# AUDIO.net
KiCad netlist of a schematic drawn in Altium Designer
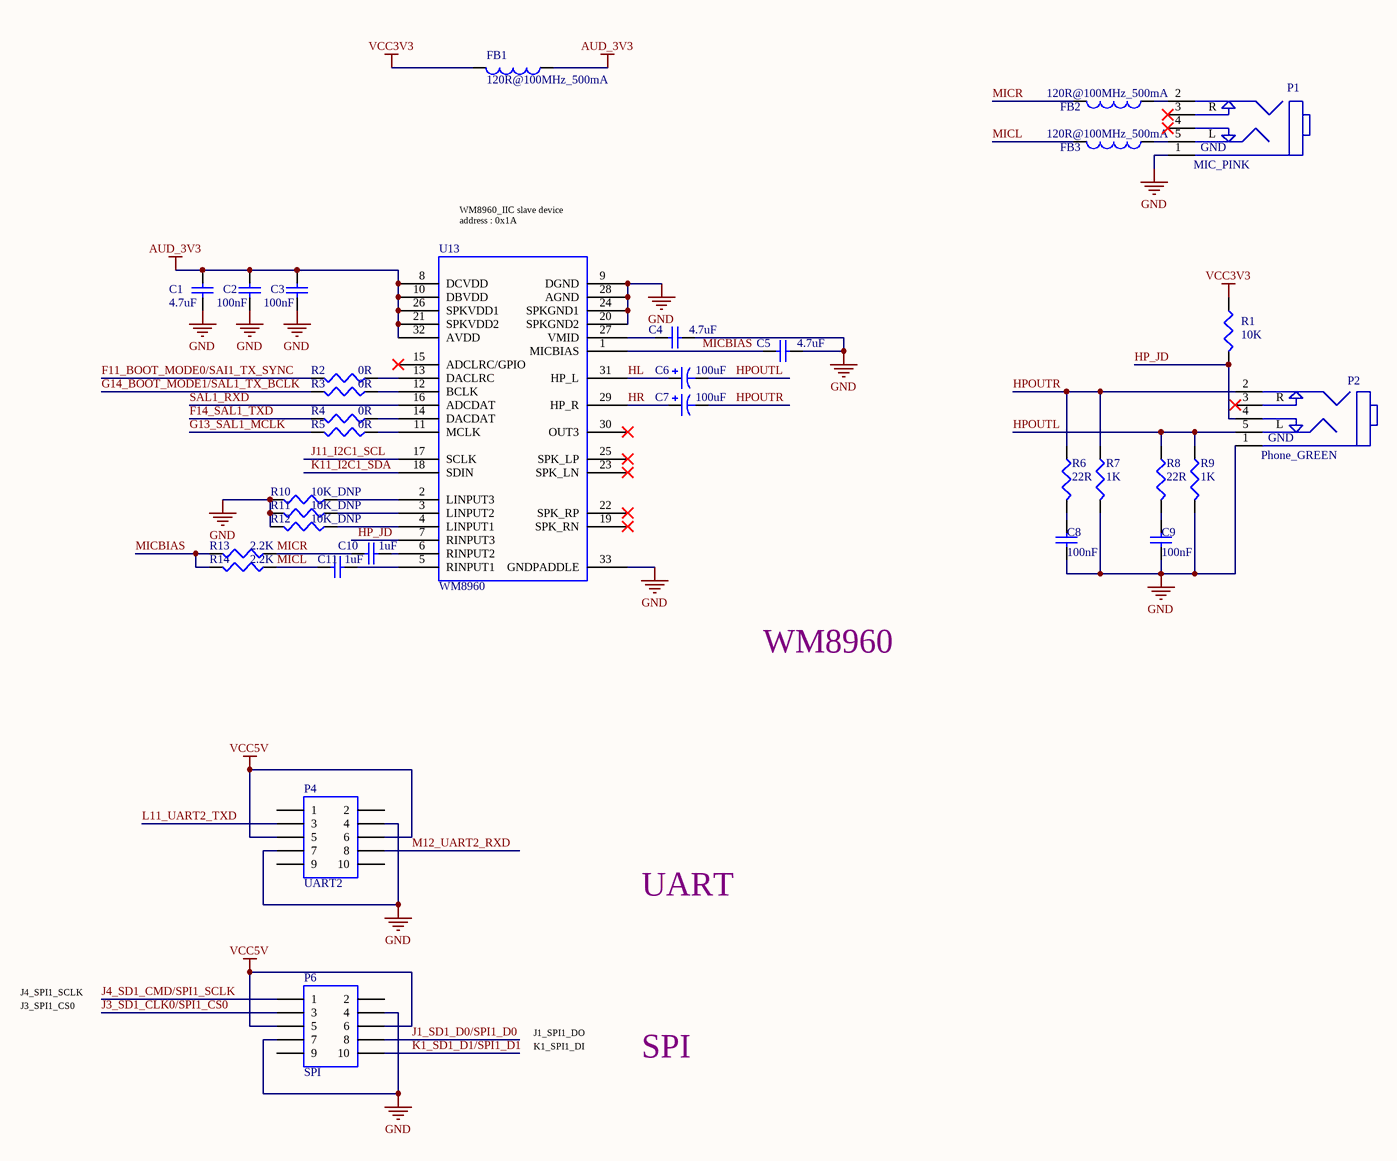
[diagram p0: AUDIO.SchDoc]

(export (version "E")
  (design (tool "Eeschema 10.0.6"))
  (components
    (comp (ref "C1")
      (value "4.7uF")
      (footprint "0603C+")
      (description "Capacitor")
      (fields (field (name "PUBLISHER") "Altium Limited"))
      (libsource (lib "Miscellaneous Devices") (part "Cap"))
    )
    (comp (ref "C2")
      (value "100nF")
      (footprint "0603C+")
      (description "Capacitor")
      (fields (field (name "PUBLISHER") "Altium Limited"))
      (libsource (lib "Miscellaneous Devices") (part "Cap"))
    )
    (comp (ref "C3")
      (value "100nF")
      (footprint "0603C+")
      (description "Capacitor")
      (fields (field (name "PUBLISHER") "Altium Limited"))
      (libsource (lib "Miscellaneous Devices") (part "Cap"))
    )
    (comp (ref "C4")
      (value "4.7uF")
      (footprint "0603C+")
      (description "Capacitor")
      (fields (field (name "PUBLISHER") "Altium Limited"))
      (libsource (lib "Miscellaneous Devices") (part "Cap"))
    )
    (comp (ref "C5")
      (value "4.7uF")
      (footprint "0603C+")
      (description "Capacitor")
      (fields (field (name "PUBLISHER") "Altium Limited"))
      (libsource (lib "Miscellaneous Devices") (part "Cap"))
    )
    (comp (ref "C6")
      (value "100uF")
      (footprint "TC3528B")
      (description "Polarized Capacitor (Radial)")
      (fields (field (name "PUBLISHER") "Altium Limited"))
      (libsource (lib "Miscellaneous Devices") (part "Cap Pol1"))
    )
    (comp (ref "C7")
      (value "100uF")
      (footprint "TC3528B")
      (description "Polarized Capacitor (Radial)")
      (fields (field (name "PUBLISHER") "Altium Limited"))
      (libsource (lib "Miscellaneous Devices") (part "Cap Pol1"))
    )
    (comp (ref "C8")
      (value "100nF")
      (footprint "0603C+")
      (description "Capacitor")
      (fields (field (name "PUBLISHER") "Altium Limited"))
      (libsource (lib "Miscellaneous Devices") (part "Cap"))
    )
    (comp (ref "C9")
      (value "100nF")
      (footprint "0603C+")
      (description "Capacitor")
      (fields (field (name "PUBLISHER") "Altium Limited"))
      (libsource (lib "Miscellaneous Devices") (part "Cap"))
    )
    (comp (ref "C10")
      (value "1uF")
      (footprint "0603C+")
      (description "Capacitor")
      (fields (field (name "PUBLISHER") "Altium Limited"))
      (libsource (lib "Miscellaneous Devices") (part "Cap"))
    )
    (comp (ref "C11")
      (value "1uF")
      (footprint "0603C+")
      (description "Capacitor")
      (fields (field (name "PUBLISHER") "Altium Limited"))
      (libsource (lib "Miscellaneous Devices") (part "Cap"))
    )
    (comp (ref "FB1")
      (value "120R@100MHz_500mA")
      (footprint "0603R+")
      (description "Inductor")
      (fields (field (name "PUBLISHER") "Altium Limited"))
      (libsource (lib "Miscellaneous Devices") (part "Inductor"))
    )
    (comp (ref "FB2")
      (value "120R@100MHz_500mA")
      (footprint "0603R+")
      (description "Inductor")
      (fields (field (name "PUBLISHER") "Altium Limited"))
      (libsource (lib "Miscellaneous Devices") (part "Inductor"))
    )
    (comp (ref "FB3")
      (value "120R@100MHz_500mA")
      (footprint "0603R+")
      (description "Inductor")
      (fields (field (name "PUBLISHER") "Altium Limited"))
      (libsource (lib "Miscellaneous Devices") (part "Inductor"))
    )
    (comp (ref "P1")
      (value "MIC_PINK")
      (footprint "PHONEJACK SW")
      (libsource (lib "Miscellaneous Devices") (part "Phonejack Stereo SW"))
    )
    (comp (ref "P2")
      (value "Phone_GREEN")
      (footprint "PHONEJACK SW")
      (libsource (lib "IMX6QP-C") (part "Phonejack Stereo SW"))
    )
    (comp (ref "P4")
      (value "UART2")
      (description "Header, 5-Pin, Dual row")
      (fields (field (name "PUBLISHER") "Altium Limited"))
      (libsource (lib "RT1060") (part "Header 5X2"))
    )
    (comp (ref "P6")
      (value "SPI")
      (description "Header, 5-Pin, Dual row")
      (fields (field (name "PUBLISHER") "Altium Limited"))
      (libsource (lib "RT1060") (part "Header 5X2"))
    )
    (comp (ref "R1")
      (value "10K")
      (footprint "0603R+")
      (description "Resistor")
      (fields (field (name "PUBLISHER") "Altium Limited"))
      (libsource (lib "Miscellaneous Devices") (part "Res3"))
    )
    (comp (ref "R2")
      (value "0R")
      (footprint "0603R+")
      (description "Resistor")
      (fields (field (name "PUBLISHER") "Altium Limited"))
      (libsource (lib "Miscellaneous Devices") (part "Res3"))
    )
    (comp (ref "R3")
      (value "0R")
      (footprint "0603R+")
      (description "Resistor")
      (fields (field (name "PUBLISHER") "Altium Limited"))
      (libsource (lib "Miscellaneous Devices") (part "Res3"))
    )
    (comp (ref "R4")
      (value "0R")
      (footprint "0603R+")
      (description "Resistor")
      (fields (field (name "PUBLISHER") "Altium Limited"))
      (libsource (lib "Miscellaneous Devices") (part "Res3"))
    )
    (comp (ref "R5")
      (value "0R")
      (footprint "0603R+")
      (description "Resistor")
      (fields (field (name "PUBLISHER") "Altium Limited"))
      (libsource (lib "Miscellaneous Devices") (part "Res3"))
    )
    (comp (ref "R6")
      (value "22R")
      (footprint "0603R+")
      (description "Resistor")
      (fields (field (name "PUBLISHER") "Altium Limited"))
      (libsource (lib "Miscellaneous Devices") (part "Res3"))
    )
    (comp (ref "R7")
      (value "1K")
      (footprint "0603R+")
      (description "Resistor")
      (fields (field (name "PUBLISHER") "Altium Limited"))
      (libsource (lib "Miscellaneous Devices") (part "Res3"))
    )
    (comp (ref "R8")
      (value "22R")
      (footprint "0603R+")
      (description "Resistor")
      (fields (field (name "PUBLISHER") "Altium Limited"))
      (libsource (lib "Miscellaneous Devices") (part "Res3"))
    )
    (comp (ref "R9")
      (value "1K")
      (footprint "0603R+")
      (description "Resistor")
      (fields (field (name "PUBLISHER") "Altium Limited"))
      (libsource (lib "Miscellaneous Devices") (part "Res3"))
    )
    (comp (ref "R10")
      (value "10K_DNP")
      (footprint "0603R+")
      (description "Resistor")
      (fields (field (name "PUBLISHER") "Altium Limited"))
      (libsource (lib "Miscellaneous Devices") (part "Res3"))
    )
    (comp (ref "R11")
      (value "10K_DNP")
      (footprint "0603R+")
      (description "Resistor")
      (fields (field (name "PUBLISHER") "Altium Limited"))
      (libsource (lib "Miscellaneous Devices") (part "Res3"))
    )
    (comp (ref "R12")
      (value "10K_DNP")
      (footprint "0603R+")
      (description "Resistor")
      (fields (field (name "PUBLISHER") "Altium Limited"))
      (libsource (lib "Miscellaneous Devices") (part "Res3"))
    )
    (comp (ref "R13")
      (value "2.2K")
      (footprint "0603R+")
      (description "Resistor")
      (fields (field (name "PUBLISHER") "Altium Limited"))
      (libsource (lib "Miscellaneous Devices") (part "Res3"))
    )
    (comp (ref "R14")
      (value "2.2K")
      (footprint "0603R+")
      (description "Resistor")
      (fields (field (name "PUBLISHER") "Altium Limited"))
      (libsource (lib "Miscellaneous Devices") (part "Res3"))
    )
    (comp (ref "U13") (value "WM8960") (footprint "WM8960") (libsource (lib "IMX6QP-C") (part "WM8960")))
  )
  (nets
    (net (code "1") (name "/F11_BOOT_MODE0{slash}SAI1_TX_SYNC") (class "Default")
      (node (ref "R2") (pin "2") (pinfunction "2_2") (pintype "passive"))
    )
    (net (code "2") (name "/F14_SAL1_TXD") (class "Default")
      (node (ref "R4") (pin "2") (pinfunction "2_2") (pintype "passive"))
    )
    (net (code "3") (name "/G13_SAL1_MCLK") (class "Default")
      (node (ref "R5") (pin "2") (pinfunction "2_2") (pintype "passive"))
    )
    (net (code "4") (name "/G14_BOOT_MODE1{slash}SAL1_TX_BCLK") (class "Default")
      (node (ref "R3") (pin "2") (pinfunction "2_2") (pintype "passive"))
    )
    (net (code "5") (name "/HL") (class "Default")
      (node (ref "C6") (pin "1") (pinfunction "1_1") (pintype "passive"))
      (node (ref "U13") (pin "31") (pinfunction "HP_L_31") (pintype "passive"))
    )
    (net (code "6") (name "/HPOUTL") (class "Default")
      (node (ref "C6") (pin "2") (pinfunction "2_2") (pintype "passive"))
      (node (ref "P2") (pin "5") (pinfunction "5_5") (pintype "passive"))
      (node (ref "R8") (pin "1") (pinfunction "1_1") (pintype "passive"))
      (node (ref "R9") (pin "1") (pinfunction "1_1") (pintype "passive"))
    )
    (net (code "7") (name "/HPOUTR") (class "Default")
      (node (ref "C7") (pin "2") (pinfunction "2_2") (pintype "passive"))
      (node (ref "P2") (pin "2") (pinfunction "2_2") (pintype "passive"))
      (node (ref "R6") (pin "1") (pinfunction "1_1") (pintype "passive"))
      (node (ref "R7") (pin "1") (pinfunction "1_1") (pintype "passive"))
    )
    (net (code "8") (name "/HP_JD") (class "Default")
      (node (ref "P2") (pin "4") (pinfunction "4_4") (pintype "passive"))
      (node (ref "R1") (pin "2") (pinfunction "2_2") (pintype "passive"))
      (node (ref "U13") (pin "7") (pinfunction "RINPUT3_7") (pintype "passive"))
    )
    (net (code "9") (name "/HR") (class "Default")
      (node (ref "C7") (pin "1") (pinfunction "1_1") (pintype "passive"))
      (node (ref "U13") (pin "29") (pinfunction "HP_R_29") (pintype "passive"))
    )
    (net (code "10") (name "/J1_SD1_D0{slash}SPI1_D0") (class "Default")
      (node (ref "P6") (pin "8") (pinfunction "8_8") (pintype "passive"))
    )
    (net (code "12") (name "/J3_SD1_CLK0{slash}SPI1_CS0") (class "Default")
      (node (ref "P6") (pin "3") (pinfunction "3_3") (pintype "passive"))
    )
    (net (code "14") (name "/J4_SD1_CMD{slash}SPI1_SCLK") (class "Default")
      (node (ref "P6") (pin "1") (pinfunction "1_1") (pintype "passive"))
    )
    (net (code "16") (name "/J11_I2C1_SCL") (class "Default")
      (node (ref "U13") (pin "17") (pinfunction "SCLK_17") (pintype "passive"))
    )
    (net (code "17") (name "/K1_SD1_D1{slash}SPI1_D1") (class "Default")
      (node (ref "P6") (pin "10") (pinfunction "10_10") (pintype "passive"))
    )
    (net (code "19") (name "/K11_I2C1_SDA") (class "Default")
      (node (ref "U13") (pin "18") (pinfunction "SDIN_18") (pintype "passive"))
    )
    (net (code "20") (name "/L11_UART2_TXD") (class "Default")
      (node (ref "P4") (pin "3") (pinfunction "3_3") (pintype "passive"))
    )
    (net (code "21") (name "/M12_UART2_RXD") (class "Default")
      (node (ref "P4") (pin "8") (pinfunction "8_8") (pintype "passive"))
    )
    (net (code "22") (name "/MICBIAS") (class "Default")
      (node (ref "C5") (pin "2") (pinfunction "2_2") (pintype "passive"))
      (node (ref "R13") (pin "2") (pinfunction "2_2") (pintype "passive"))
      (node (ref "R14") (pin "2") (pinfunction "2_2") (pintype "passive"))
      (node (ref "U13") (pin "1") (pinfunction "MICBIAS_1") (pintype "passive"))
    )
    (net (code "23") (name "/MICL") (class "Default")
      (node (ref "C11") (pin "2") (pinfunction "2_2") (pintype "passive"))
      (node (ref "FB3") (pin "2") (pinfunction "2_2") (pintype "passive"))
      (node (ref "R14") (pin "1") (pinfunction "1_1") (pintype "passive"))
    )
    (net (code "24") (name "/MICR") (class "Default")
      (node (ref "C10") (pin "2") (pinfunction "2_2") (pintype "passive"))
      (node (ref "FB2") (pin "2") (pinfunction "2_2") (pintype "passive"))
      (node (ref "R13") (pin "1") (pinfunction "1_1") (pintype "passive"))
    )
    (net (code "25") (name "/SAL1_RXD") (class "Default")
      (node (ref "U13") (pin "16") (pinfunction "ADCDAT_16") (pintype "passive"))
    )
    (net (code "26") (name "AUD_3V3") (class "Default")
      (node (ref "C1") (pin "2") (pinfunction "2_2") (pintype "passive"))
      (node (ref "C2") (pin "2") (pinfunction "2_2") (pintype "passive"))
      (node (ref "C3") (pin "2") (pinfunction "2_2") (pintype "passive"))
      (node (ref "FB1") (pin "1") (pinfunction "1_1") (pintype "passive"))
      (node (ref "U13") (pin "10") (pinfunction "DBVDD_10") (pintype "passive"))
      (node (ref "U13") (pin "21") (pinfunction "SPKVDD2_21") (pintype "passive"))
      (node (ref "U13") (pin "26") (pinfunction "SPKVDD1_26") (pintype "passive"))
      (node (ref "U13") (pin "32") (pinfunction "AVDD_32") (pintype "passive"))
      (node (ref "U13") (pin "8") (pinfunction "DCVDD_8") (pintype "passive"))
    )
    (net (code "27") (name "GND") (class "Default")
      (node (ref "C1") (pin "1") (pinfunction "1_1") (pintype "passive"))
      (node (ref "C2") (pin "1") (pinfunction "1_1") (pintype "passive"))
      (node (ref "C3") (pin "1") (pinfunction "1_1") (pintype "passive"))
      (node (ref "C4") (pin "1") (pinfunction "1_1") (pintype "passive"))
      (node (ref "C5") (pin "1") (pinfunction "1_1") (pintype "passive"))
      (node (ref "C8") (pin "2") (pinfunction "2_2") (pintype "passive"))
      (node (ref "C9") (pin "2") (pinfunction "2_2") (pintype "passive"))
      (node (ref "P1") (pin "1") (pinfunction "GND_1") (pintype "passive"))
      (node (ref "P2") (pin "1") (pinfunction "GND_1") (pintype "passive"))
      (node (ref "P4") (pin "4") (pinfunction "4_4") (pintype "passive"))
      (node (ref "P4") (pin "7") (pinfunction "7_7") (pintype "passive"))
      (node (ref "P6") (pin "4") (pinfunction "4_4") (pintype "passive"))
      (node (ref "P6") (pin "7") (pinfunction "7_7") (pintype "passive"))
      (node (ref "R10") (pin "2") (pinfunction "2_2") (pintype "passive"))
      (node (ref "R11") (pin "2") (pinfunction "2_2") (pintype "passive"))
      (node (ref "R12") (pin "2") (pinfunction "2_2") (pintype "passive"))
      (node (ref "R7") (pin "2") (pinfunction "2_2") (pintype "passive"))
      (node (ref "R9") (pin "2") (pinfunction "2_2") (pintype "passive"))
      (node (ref "U13") (pin "20") (pinfunction "SPKGND2_20") (pintype "passive"))
      (node (ref "U13") (pin "24") (pinfunction "SPKGND1_24") (pintype "passive"))
      (node (ref "U13") (pin "28") (pinfunction "AGND_28") (pintype "passive"))
      (node (ref "U13") (pin "33") (pinfunction "GNDPADDLE_33") (pintype "passive"))
      (node (ref "U13") (pin "9") (pinfunction "DGND_9") (pintype "passive"))
    )
    (net (code "28") (name "Net-(C8-Pad1)") (class "Default")
      (node (ref "C8") (pin "1") (pinfunction "1_1") (pintype "passive"))
      (node (ref "R6") (pin "2") (pinfunction "2_2") (pintype "passive"))
    )
    (net (code "29") (name "Net-(C9-Pad1)") (class "Default")
      (node (ref "C9") (pin "1") (pinfunction "1_1") (pintype "passive"))
      (node (ref "R8") (pin "2") (pinfunction "2_2") (pintype "passive"))
    )
    (net (code "30") (name "Net-(FB2-Pad1)") (class "Default")
      (node (ref "FB2") (pin "1") (pinfunction "1_1") (pintype "passive"))
      (node (ref "P1") (pin "2") (pinfunction "2_2") (pintype "passive"))
    )
    (net (code "31") (name "Net-(FB3-Pad1)") (class "Default")
      (node (ref "FB3") (pin "1") (pinfunction "1_1") (pintype "passive"))
      (node (ref "P1") (pin "5") (pinfunction "5_5") (pintype "passive"))
    )
    (net (code "32") (name "Net-(U13-BCLK)") (class "Default")
      (node (ref "R3") (pin "1") (pinfunction "1_1") (pintype "passive"))
      (node (ref "U13") (pin "12") (pinfunction "BCLK_12") (pintype "passive"))
    )
    (net (code "33") (name "Net-(U13-DACDAT)") (class "Default")
      (node (ref "R4") (pin "1") (pinfunction "1_1") (pintype "passive"))
      (node (ref "U13") (pin "14") (pinfunction "DACDAT_14") (pintype "passive"))
    )
    (net (code "34") (name "Net-(U13-DACLRC)") (class "Default")
      (node (ref "R2") (pin "1") (pinfunction "1_1") (pintype "passive"))
      (node (ref "U13") (pin "13") (pinfunction "DACLRC_13") (pintype "passive"))
    )
    (net (code "35") (name "Net-(U13-LINPUT1)") (class "Default")
      (node (ref "R12") (pin "1") (pinfunction "1_1") (pintype "passive"))
      (node (ref "U13") (pin "4") (pinfunction "LINPUT1_4") (pintype "passive"))
    )
    (net (code "36") (name "Net-(U13-LINPUT2)") (class "Default")
      (node (ref "R11") (pin "1") (pinfunction "1_1") (pintype "passive"))
      (node (ref "U13") (pin "3") (pinfunction "LINPUT2_3") (pintype "passive"))
    )
    (net (code "37") (name "Net-(U13-LINPUT3)") (class "Default")
      (node (ref "R10") (pin "1") (pinfunction "1_1") (pintype "passive"))
      (node (ref "U13") (pin "2") (pinfunction "LINPUT3_2") (pintype "passive"))
    )
    (net (code "38") (name "Net-(U13-MCLK)") (class "Default")
      (node (ref "R5") (pin "1") (pinfunction "1_1") (pintype "passive"))
      (node (ref "U13") (pin "11") (pinfunction "MCLK_11") (pintype "passive"))
    )
    (net (code "39") (name "Net-(U13-RINPUT1)") (class "Default")
      (node (ref "C11") (pin "1") (pinfunction "1_1") (pintype "passive"))
      (node (ref "U13") (pin "5") (pinfunction "RINPUT1_5") (pintype "passive"))
    )
    (net (code "40") (name "Net-(U13-RINPUT2)") (class "Default")
      (node (ref "C10") (pin "1") (pinfunction "1_1") (pintype "passive"))
      (node (ref "U13") (pin "6") (pinfunction "RINPUT2_6") (pintype "passive"))
    )
    (net (code "41") (name "Net-(U13-VMID)") (class "Default")
      (node (ref "C4") (pin "2") (pinfunction "2_2") (pintype "passive"))
      (node (ref "U13") (pin "27") (pinfunction "VMID_27") (pintype "passive"))
    )
    (net (code "42") (name "VCC3V3") (class "Default")
      (node (ref "FB1") (pin "2") (pinfunction "2_2") (pintype "passive"))
      (node (ref "R1") (pin "1") (pinfunction "1_1") (pintype "passive"))
    )
    (net (code "43") (name "VCC5V") (class "Default")
      (node (ref "P4") (pin "5") (pinfunction "5_5") (pintype "passive"))
      (node (ref "P4") (pin "6") (pinfunction "6_6") (pintype "passive"))
      (node (ref "P6") (pin "5") (pinfunction "5_5") (pintype "passive"))
      (node (ref "P6") (pin "6") (pinfunction "6_6") (pintype "passive"))
    )
    (net (code "44") (name "unconnected-(P1-Pad3)") (class "Default")
      (node (ref "P1") (pin "3") (pinfunction "3_3") (pintype "passive+no_connect"))
    )
    (net (code "45") (name "unconnected-(P1-Pad4)") (class "Default")
      (node (ref "P1") (pin "4") (pinfunction "4_4") (pintype "passive+no_connect"))
    )
    (net (code "46") (name "unconnected-(P2-Pad3)") (class "Default")
      (node (ref "P2") (pin "3") (pinfunction "3_3") (pintype "passive+no_connect"))
    )
    (net (code "47") (name "unconnected-(P4-Pad1)") (class "Default")
      (node (ref "P4") (pin "1") (pinfunction "1_1") (pintype "passive"))
    )
    (net (code "48") (name "unconnected-(P4-Pad2)") (class "Default")
      (node (ref "P4") (pin "2") (pinfunction "2_2") (pintype "passive"))
    )
    (net (code "49") (name "unconnected-(P4-Pad9)") (class "Default")
      (node (ref "P4") (pin "9") (pinfunction "9_9") (pintype "passive"))
    )
    (net (code "50") (name "unconnected-(P4-Pad10)") (class "Default")
      (node (ref "P4") (pin "10") (pinfunction "10_10") (pintype "passive"))
    )
    (net (code "51") (name "unconnected-(P6-Pad2)") (class "Default")
      (node (ref "P6") (pin "2") (pinfunction "2_2") (pintype "passive"))
    )
    (net (code "52") (name "unconnected-(P6-Pad9)") (class "Default")
      (node (ref "P6") (pin "9") (pinfunction "9_9") (pintype "passive"))
    )
    (net (code "53") (name "unconnected-(U13-ADCLRC{slash}GPIO-Pad15)") (class "Default")
      (node (ref "U13") (pin "15") (pinfunction "ADCLRC/GPIO_15") (pintype "passive+no_connect"))
    )
    (net (code "54") (name "unconnected-(U13-OUT3-Pad30)") (class "Default")
      (node (ref "U13") (pin "30") (pinfunction "OUT3_30") (pintype "passive+no_connect"))
    )
    (net (code "55") (name "unconnected-(U13-SPK_LN-Pad23)") (class "Default")
      (node (ref "U13") (pin "23") (pinfunction "SPK_LN_23") (pintype "passive+no_connect"))
    )
    (net (code "56") (name "unconnected-(U13-SPK_LP-Pad25)") (class "Default")
      (node (ref "U13") (pin "25") (pinfunction "SPK_LP_25") (pintype "passive+no_connect"))
    )
    (net (code "57") (name "unconnected-(U13-SPK_RN-Pad19)") (class "Default")
      (node (ref "U13") (pin "19") (pinfunction "SPK_RN_19") (pintype "passive+no_connect"))
    )
    (net (code "58") (name "unconnected-(U13-SPK_RP-Pad22)") (class "Default")
      (node (ref "U13") (pin "22") (pinfunction "SPK_RP_22") (pintype "passive+no_connect"))
    )
  )
)
